# CAN-BUS_Shield_v0_9b.net
KiCad netlist of a schematic drawn in EAGLE
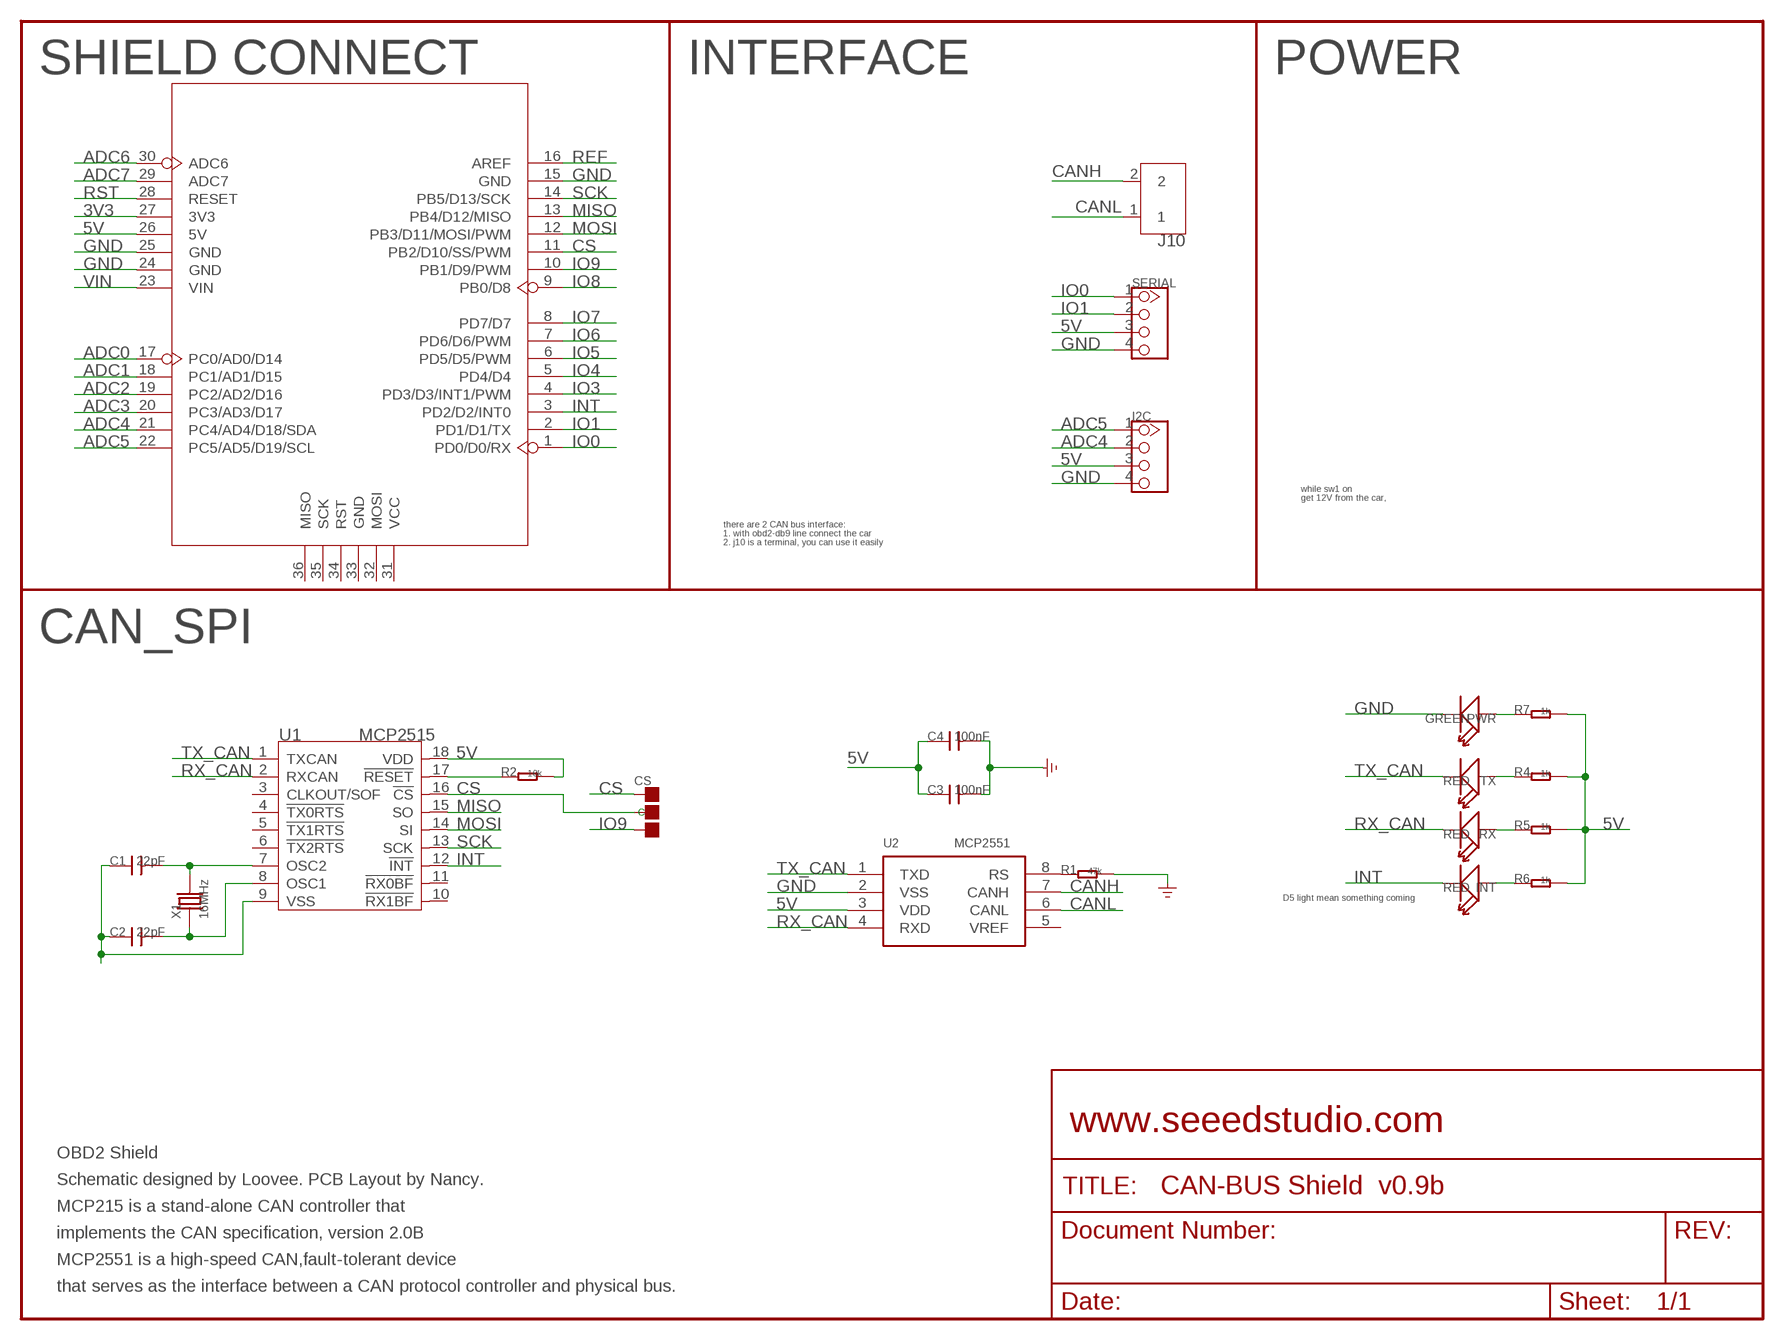
[diagram p0: schematic, sheet 1]

(export (version "E")
  (design (tool "Eeschema 10.0.6"))
  (components
    (comp (ref "C1")
      (value "22pF")
      (footprint "eagle-import:0603")
      (libsource (lib "eagle-import") (part "C-0603"))
    )
    (comp (ref "C2")
      (value "22pF")
      (footprint "eagle-import:0603")
      (libsource (lib "eagle-import") (part "C-0603"))
    )
    (comp (ref "C3")
      (value "100nF")
      (footprint "eagle-import:0603")
      (libsource (lib "eagle-import") (part "C-0603"))
    )
    (comp (ref "C4")
      (value "100nF")
      (footprint "eagle-import:0603")
      (libsource (lib "eagle-import") (part "C-0603"))
    )
    (comp (ref "CS")
      (value "PAD-JUMPER-3P-40*40")
      (footprint "eagle-import:3P-SMD-4.1X1.5")
      (libsource (lib "eagle-import") (part "PAD-JUMPER-3P-4040"))
    )
    (comp (ref "I2C")
      (value "TWIG-4P-2.0-2.0")
      (footprint "eagle-import:4P-2.0")
      (libsource (lib "eagle-import") (part "TWIG-4P-2.0-2.0"))
    )
    (comp (ref "INT")
      (value "RED")
      (footprint "eagle-import:LED-0603")
      (libsource (lib "eagle-import") (part "LED'0603'"))
    )
    (comp (ref "J10")
      (value "SCREW-TERMINAL-2P5.0")
      (footprint "eagle-import:2P-5.0")
      (libsource (lib "eagle-import") (part "SCREW-TERMINAL-2P5.0"))
    )
    (comp (ref "PWR")
      (value "GREEN")
      (footprint "eagle-import:LED-0603")
      (libsource (lib "eagle-import") (part "LED'0603'"))
    )
    (comp (ref "R1")
      (value "47k")
      (footprint "eagle-import:0603")
      (libsource (lib "eagle-import") (part "R-0603"))
    )
    (comp (ref "R2")
      (value "10k")
      (footprint "eagle-import:0603")
      (libsource (lib "eagle-import") (part "R-0603"))
    )
    (comp (ref "R4")
      (value "1k")
      (footprint "eagle-import:0603")
      (libsource (lib "eagle-import") (part "R-0603"))
    )
    (comp (ref "R5")
      (value "1k")
      (footprint "eagle-import:0603")
      (libsource (lib "eagle-import") (part "R-0603"))
    )
    (comp (ref "R6")
      (value "1k")
      (footprint "eagle-import:0603")
      (libsource (lib "eagle-import") (part "R-0603"))
    )
    (comp (ref "R7")
      (value "1k")
      (footprint "eagle-import:0603")
      (libsource (lib "eagle-import") (part "R-0603"))
    )
    (comp (ref "RX")
      (value "RED")
      (footprint "eagle-import:LED-0603")
      (libsource (lib "eagle-import") (part "LED'0603'"))
    )
    (comp (ref "SERIAL")
      (value "TWIG-4P-2.0-2.0")
      (footprint "eagle-import:4P-2.0")
      (libsource (lib "eagle-import") (part "TWIG-4P-2.0-2.0"))
    )
    (comp (ref "TX")
      (value "RED")
      (footprint "eagle-import:LED-0603")
      (libsource (lib "eagle-import") (part "LED'0603'"))
    )
    (comp (ref "U1")
      (value "MCP2515")
      (footprint "eagle-import:SOIC18")
      (libsource (lib "eagle-import") (part "MCP2515"))
    )
    (comp (ref "U2")
      (value "MCP2551")
      (footprint "eagle-import:SO08")
      (libsource (lib "eagle-import") (part "MCP2551"))
    )
    (comp (ref "U3")
      (value "ARDUINO")
      (footprint "eagle-import:ARDUINO")
      (libsource (lib "eagle-import") (part "ARDUINO"))
    )
    (comp (ref "X1")
      (value "16MHz")
      (footprint "eagle-import:HC49_S")
      (libsource (lib "eagle-import") (part "CRYSTAL-HC49S"))
    )
  )
  (nets
    (net (code "1") (name "/3V3") (class "Default")
      (node (ref "U3") (pin "27") (pinfunction "3V3_27") (pintype "bidirectional"))
    )
    (net (code "2") (name "/5V") (class "Default")
      (node (ref "C3") (pin "1") (pinfunction "1_1") (pintype "passive"))
      (node (ref "C4") (pin "1") (pinfunction "1_1") (pintype "passive"))
      (node (ref "I2C") (pin "3") (pinfunction "3_3") (pintype "bidirectional"))
      (node (ref "R2") (pin "2") (pinfunction "2_2") (pintype "passive"))
      (node (ref "R4") (pin "2") (pinfunction "2_2") (pintype "passive"))
      (node (ref "R5") (pin "2") (pinfunction "2_2") (pintype "passive"))
      (node (ref "R6") (pin "2") (pinfunction "2_2") (pintype "passive"))
      (node (ref "R7") (pin "2") (pinfunction "2_2") (pintype "passive"))
      (node (ref "SERIAL") (pin "3") (pinfunction "3_3") (pintype "bidirectional"))
      (node (ref "U1") (pin "18") (pinfunction "VDD_18") (pintype "power_in"))
      (node (ref "U2") (pin "3") (pinfunction "VDD_3") (pintype "bidirectional"))
      (node (ref "U3") (pin "26") (pinfunction "5V_26") (pintype "bidirectional"))
    )
    (net (code "3") (name "/ADC0") (class "Default")
      (node (ref "U3") (pin "17") (pinfunction "PC0/AD0/D14_17") (pintype "bidirectional"))
    )
    (net (code "4") (name "/ADC1") (class "Default")
      (node (ref "U3") (pin "18") (pinfunction "PC1/AD1/D15_18") (pintype "bidirectional"))
    )
    (net (code "5") (name "/ADC2") (class "Default")
      (node (ref "U3") (pin "19") (pinfunction "PC2/AD2/D16_19") (pintype "bidirectional"))
    )
    (net (code "6") (name "/ADC3") (class "Default")
      (node (ref "U3") (pin "20") (pinfunction "PC3/AD3/D17_20") (pintype "bidirectional"))
    )
    (net (code "7") (name "/ADC4") (class "Default")
      (node (ref "I2C") (pin "2") (pinfunction "2_2") (pintype "bidirectional"))
      (node (ref "U3") (pin "21") (pinfunction "PC4/AD4/D18/SDA_21") (pintype "bidirectional"))
    )
    (net (code "8") (name "/ADC5") (class "Default")
      (node (ref "I2C") (pin "1") (pinfunction "1_1") (pintype "bidirectional"))
      (node (ref "U3") (pin "22") (pinfunction "PC5/AD5/D19/SCL_22") (pintype "bidirectional"))
    )
    (net (code "9") (name "/ADC6") (class "Default")
      (node (ref "U3") (pin "30") (pinfunction "ADC6_30") (pintype "bidirectional"))
    )
    (net (code "10") (name "/ADC7") (class "Default")
      (node (ref "U3") (pin "29") (pinfunction "ADC7_29") (pintype "bidirectional"))
    )
    (net (code "11") (name "/CANH") (class "Default")
      (node (ref "J10") (pin "2") (pinfunction "2_2") (pintype "bidirectional"))
      (node (ref "U2") (pin "7") (pinfunction "CANH_7") (pintype "bidirectional"))
    )
    (net (code "12") (name "/CANL") (class "Default")
      (node (ref "J10") (pin "1") (pinfunction "1_1") (pintype "bidirectional"))
      (node (ref "U2") (pin "6") (pinfunction "CANL_6") (pintype "bidirectional"))
    )
    (net (code "13") (name "/CS") (class "Default")
      (node (ref "CS") (pin "00") (pinfunction "L_00") (pintype "bidirectional"))
      (node (ref "CS") (pin "MM") (pinfunction "C_MM") (pintype "bidirectional"))
      (node (ref "U1") (pin "16") (pinfunction "~{CS}_16") (pintype "input"))
      (node (ref "U3") (pin "11") (pinfunction "PB2/D10/SS/PWM_11") (pintype "bidirectional"))
    )
    (net (code "14") (name "/INT") (class "Default")
      (node (ref "INT") (pin "-") (pinfunction "-_-") (pintype "passive"))
      (node (ref "U1") (pin "12") (pinfunction "~{INT}_12") (pintype "output"))
      (node (ref "U3") (pin "3") (pinfunction "PD2/D2/INT0_3") (pintype "bidirectional"))
    )
    (net (code "15") (name "/IO0") (class "Default")
      (node (ref "SERIAL") (pin "1") (pinfunction "1_1") (pintype "bidirectional"))
      (node (ref "U3") (pin "1") (pinfunction "PD0/D0/RX_1") (pintype "bidirectional"))
    )
    (net (code "16") (name "/IO1") (class "Default")
      (node (ref "SERIAL") (pin "2") (pinfunction "2_2") (pintype "bidirectional"))
      (node (ref "U3") (pin "2") (pinfunction "PD1/D1/TX_2") (pintype "bidirectional"))
    )
    (net (code "17") (name "/IO3") (class "Default")
      (node (ref "U3") (pin "4") (pinfunction "PD3/D3/INT1/PWM_4") (pintype "bidirectional"))
    )
    (net (code "18") (name "/IO4") (class "Default")
      (node (ref "U3") (pin "5") (pinfunction "PD4/D4_5") (pintype "bidirectional"))
    )
    (net (code "19") (name "/IO5") (class "Default")
      (node (ref "U3") (pin "6") (pinfunction "PD5/D5/PWM_6") (pintype "bidirectional"))
    )
    (net (code "20") (name "/IO6") (class "Default")
      (node (ref "U3") (pin "7") (pinfunction "PD6/D6/PWM_7") (pintype "bidirectional"))
    )
    (net (code "21") (name "/IO7") (class "Default")
      (node (ref "U3") (pin "8") (pinfunction "PD7/D7_8") (pintype "bidirectional"))
    )
    (net (code "22") (name "/IO8") (class "Default")
      (node (ref "U3") (pin "9") (pinfunction "PB0/D8_9") (pintype "bidirectional"))
    )
    (net (code "23") (name "/IO9") (class "Default")
      (node (ref "CS") (pin "11") (pinfunction "R_11") (pintype "bidirectional"))
      (node (ref "U3") (pin "10") (pinfunction "PB1/D9/PWM_10") (pintype "bidirectional"))
    )
    (net (code "24") (name "/MISO") (class "Default")
      (node (ref "U1") (pin "15") (pinfunction "SO_15") (pintype "output"))
      (node (ref "U3") (pin "13") (pinfunction "PB4/D12/MISO_13") (pintype "bidirectional"))
    )
    (net (code "25") (name "/MOSI") (class "Default")
      (node (ref "U1") (pin "14") (pinfunction "SI_14") (pintype "input"))
      (node (ref "U3") (pin "12") (pinfunction "PB3/D11/MOSI/PWM_12") (pintype "bidirectional"))
    )
    (net (code "26") (name "/REF") (class "Default")
      (node (ref "U3") (pin "16") (pinfunction "AREF_16") (pintype "bidirectional"))
    )
    (net (code "27") (name "/RST") (class "Default")
      (node (ref "U3") (pin "28") (pinfunction "RESET_28") (pintype "bidirectional"))
    )
    (net (code "28") (name "/RX_CAN") (class "Default")
      (node (ref "RX") (pin "-") (pinfunction "-_-") (pintype "passive"))
      (node (ref "U1") (pin "2") (pinfunction "RXCAN_2") (pintype "input"))
      (node (ref "U2") (pin "4") (pinfunction "RXD_4") (pintype "bidirectional"))
    )
    (net (code "29") (name "/SCK") (class "Default")
      (node (ref "U1") (pin "13") (pinfunction "SCK_13") (pintype "input"))
      (node (ref "U3") (pin "14") (pinfunction "PB5/D13/SCK_14") (pintype "bidirectional"))
    )
    (net (code "30") (name "/TX_CAN") (class "Default")
      (node (ref "TX") (pin "-") (pinfunction "-_-") (pintype "passive"))
      (node (ref "U1") (pin "1") (pinfunction "TXCAN_1") (pintype "output"))
      (node (ref "U2") (pin "1") (pinfunction "TXD_1") (pintype "bidirectional"))
    )
    (net (code "31") (name "/VIN") (class "Default")
      (node (ref "U3") (pin "23") (pinfunction "VIN_23") (pintype "bidirectional"))
    )
    (net (code "32") (name "GND_POWER") (class "Default")
      (node (ref "C3") (pin "2") (pinfunction "2_2") (pintype "passive"))
      (node (ref "C4") (pin "2") (pinfunction "2_2") (pintype "passive"))
      (node (ref "I2C") (pin "4") (pinfunction "4_4") (pintype "bidirectional"))
      (node (ref "PWR") (pin "-") (pinfunction "-_-") (pintype "passive"))
      (node (ref "R1") (pin "2") (pinfunction "2_2") (pintype "passive"))
      (node (ref "SERIAL") (pin "4") (pinfunction "4_4") (pintype "bidirectional"))
      (node (ref "U2") (pin "2") (pinfunction "VSS_2") (pintype "bidirectional"))
      (node (ref "U3") (pin "15") (pinfunction "GND_15") (pintype "bidirectional"))
      (node (ref "U3") (pin "24") (pinfunction "GND_24") (pintype "bidirectional"))
      (node (ref "U3") (pin "25") (pinfunction "GND_25") (pintype "bidirectional"))
    )
    (net (code "33") (name "Net-(INT-Pad+)") (class "Default")
      (node (ref "INT") (pin "+") (pinfunction "+_+") (pintype "passive"))
      (node (ref "R6") (pin "1") (pinfunction "1_1") (pintype "passive"))
    )
    (net (code "34") (name "Net-(PWR-Pad+)") (class "Default")
      (node (ref "PWR") (pin "+") (pinfunction "+_+") (pintype "passive"))
      (node (ref "R7") (pin "1") (pinfunction "1_1") (pintype "passive"))
    )
    (net (code "35") (name "Net-(R4-Pad1)") (class "Default")
      (node (ref "R4") (pin "1") (pinfunction "1_1") (pintype "passive"))
      (node (ref "TX") (pin "+") (pinfunction "+_+") (pintype "passive"))
    )
    (net (code "36") (name "Net-(R5-Pad1)") (class "Default")
      (node (ref "R5") (pin "1") (pinfunction "1_1") (pintype "passive"))
      (node (ref "RX") (pin "+") (pinfunction "+_+") (pintype "passive"))
    )
    (net (code "37") (name "Net-(U1-OSC1)") (class "Default")
      (node (ref "C2") (pin "2") (pinfunction "2_2") (pintype "passive"))
      (node (ref "U1") (pin "8") (pinfunction "OSC1_8") (pintype "input"))
      (node (ref "X1") (pin "1") (pinfunction "1_1") (pintype "passive"))
    )
    (net (code "38") (name "Net-(U1-OSC2)") (class "Default")
      (node (ref "C1") (pin "2") (pinfunction "2_2") (pintype "passive"))
      (node (ref "U1") (pin "7") (pinfunction "OSC2_7") (pintype "output"))
      (node (ref "X1") (pin "2") (pinfunction "2_2") (pintype "passive"))
    )
    (net (code "39") (name "Net-(U1-VSS)") (class "Default")
      (node (ref "C1") (pin "1") (pinfunction "1_1") (pintype "passive"))
      (node (ref "C2") (pin "1") (pinfunction "1_1") (pintype "passive"))
      (node (ref "U1") (pin "9") (pinfunction "VSS_9") (pintype "power_in"))
    )
    (net (code "40") (name "Net-(U1-~{RESET})") (class "Default")
      (node (ref "R2") (pin "1") (pinfunction "1_1") (pintype "passive"))
      (node (ref "U1") (pin "17") (pinfunction "~{RESET}_17") (pintype "input"))
    )
    (net (code "41") (name "Net-(U2-RS)") (class "Default")
      (node (ref "R1") (pin "1") (pinfunction "1_1") (pintype "passive"))
      (node (ref "U2") (pin "8") (pinfunction "RS_8") (pintype "bidirectional"))
    )
    (net (code "42") (name "unconnected-(U1-CLKOUT{slash}SOF-Pad3)") (class "Default")
      (node (ref "U1") (pin "3") (pinfunction "CLKOUT/SOF_3") (pintype "output"))
    )
    (net (code "43") (name "unconnected-(U1-~{RX0BF}-Pad11)") (class "Default")
      (node (ref "U1") (pin "11") (pinfunction "~{RX0BF}_11") (pintype "output"))
    )
    (net (code "44") (name "unconnected-(U1-~{RX1BF}-Pad10)") (class "Default")
      (node (ref "U1") (pin "10") (pinfunction "~{RX1BF}_10") (pintype "output"))
    )
    (net (code "45") (name "unconnected-(U1-~{TX0RTS}-Pad4)") (class "Default")
      (node (ref "U1") (pin "4") (pinfunction "~{TX0RTS}_4") (pintype "input"))
    )
    (net (code "46") (name "unconnected-(U1-~{TX1RTS}-Pad5)") (class "Default")
      (node (ref "U1") (pin "5") (pinfunction "~{TX1RTS}_5") (pintype "input"))
    )
    (net (code "47") (name "unconnected-(U1-~{TX2RTS}-Pad6)") (class "Default")
      (node (ref "U1") (pin "6") (pinfunction "~{TX2RTS}_6") (pintype "input"))
    )
    (net (code "48") (name "unconnected-(U2-VREF-Pad5)") (class "Default")
      (node (ref "U2") (pin "5") (pinfunction "VREF_5") (pintype "bidirectional"))
    )
    (net (code "49") (name "unconnected-(U3-GND-Pad33)") (class "Default")
      (node (ref "U3") (pin "33") (pinfunction "GND_33") (pintype "bidirectional"))
    )
    (net (code "50") (name "unconnected-(U3-MISO-Pad36)") (class "Default")
      (node (ref "U3") (pin "36") (pinfunction "MISO_36") (pintype "bidirectional"))
    )
    (net (code "51") (name "unconnected-(U3-MOSI-Pad32)") (class "Default")
      (node (ref "U3") (pin "32") (pinfunction "MOSI_32") (pintype "bidirectional"))
    )
    (net (code "52") (name "unconnected-(U3-RST-Pad34)") (class "Default")
      (node (ref "U3") (pin "34") (pinfunction "RST_34") (pintype "bidirectional"))
    )
    (net (code "53") (name "unconnected-(U3-SCK-Pad35)") (class "Default")
      (node (ref "U3") (pin "35") (pinfunction "SCK_35") (pintype "bidirectional"))
    )
    (net (code "54") (name "unconnected-(U3-VCC-Pad31)") (class "Default")
      (node (ref "U3") (pin "31") (pinfunction "VCC_31") (pintype "bidirectional"))
    )
  )
)
